# Eth.net
KiCad netlist of a schematic drawn in Altium Designer
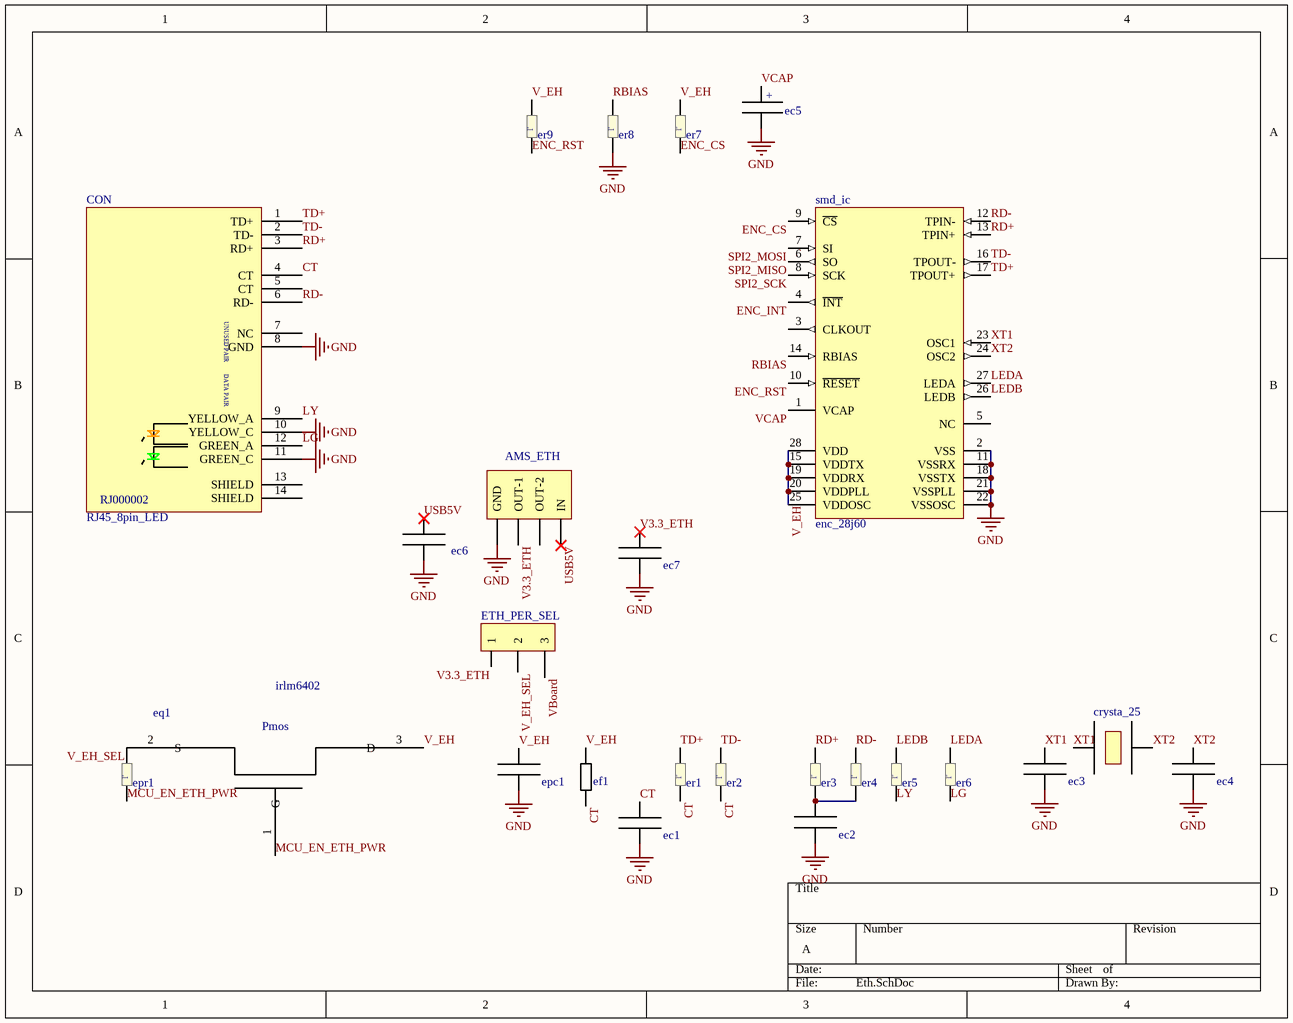
[diagram p0: Eth.SchDoc]

(export (version "E")
  (design (tool "Eeschema 10.0.6"))
  (components
    (comp (ref "AMS_ETH")
      (value "Regulator")
      (footprint "abr_fp_SOT-223_3d")
      (libsource (lib "abr_reg_smd-96-04") (part "abr_reg_AMS1117"))
    )
    (comp (ref "CON")
      (value "RJ45_8pin_LED")
      (footprint "abr_eth_RJ45_8pin_LED_3d")
      (libsource (lib "ethlib") (part "RJ45_8pin_LED"))
    )
    (comp (ref "crysta_25")
      (value "crystal")
      (footprint "abr_crystal_dip_3d")
      (libsource (lib "abr_crystal_osc_96_02") (part "abr_crystal"))
    )
    (comp (ref "ec1")
      (value "100nf")
      (footprint "abr_cap_0805_3d")
      (libsource (lib "abr_smd_0805_all") (part "abr_cap_0805"))
    )
    (comp (ref "ec2")
      (value "100nf")
      (footprint "abr_cap_0805_3d")
      (libsource (lib "abr_smd_0805_all") (part "abr_cap_0805"))
    )
    (comp (ref "ec3")
      (value "100nf")
      (footprint "abr_cap_0805_3d")
      (libsource (lib "abr_smd_0805_all") (part "abr_cap_0805"))
    )
    (comp (ref "ec4")
      (value "100nf")
      (footprint "abr_cap_0805_3d")
      (libsource (lib "abr_smd_0805_all") (part "abr_cap_0805"))
    )
    (comp (ref "ec5")
      (value "10uf")
      (footprint "abr_cap_a_3d")
      (libsource (lib "abr_capasitor") (part "abr_cap"))
    )
    (comp (ref "ec6")
      (value "1uf")
      (footprint "abr_cap_0805_3d")
      (libsource (lib "abr_smd_0805_all") (part "abr_cap_0805"))
    )
    (comp (ref "ec7")
      (value "1uf")
      (footprint "abr_cap_0805_3d")
      (libsource (lib "abr_smd_0805_all") (part "abr_cap_0805"))
    )
    (comp (ref "ef1")
      (value "smd-0805")
      (footprint "abr_fer_0805_3d")
      (libsource (lib "abr_smd_0805_all") (part "abr_fer_0805"))
    )
    (comp (ref "epc1")
      (value "100nf")
      (footprint "abr_cap_0805_3d")
      (libsource (lib "abr_smd_0805_all") (part "abr_cap_0805"))
    )
    (comp (ref "epr1")
      (value "10k")
      (footprint "abr_res_0805_3d")
      (libsource (lib "abr_smd_0805_all") (part "abr_res_0805"))
    )
    (comp (ref "eq1")
      (value "irlm6402")
      (footprint "irlm6402")
      (libsource (lib "abr_transistor_smd") (part "irlm6402"))
    )
    (comp (ref "er1")
      (value "49.9")
      (footprint "abr_res_0805_3d")
      (libsource (lib "abr_smd_0805_all") (part "abr_res_0805"))
    )
    (comp (ref "er2")
      (value "49.9")
      (footprint "abr_res_0805_3d")
      (libsource (lib "abr_smd_0805_all") (part "abr_res_0805"))
    )
    (comp (ref "er3")
      (value "49.9")
      (footprint "abr_res_0805_3d")
      (libsource (lib "abr_smd_0805_all") (part "abr_res_0805"))
    )
    (comp (ref "er4")
      (value "49.9")
      (footprint "abr_res_0805_3d")
      (libsource (lib "abr_smd_0805_all") (part "abr_res_0805"))
    )
    (comp (ref "er5")
      (value "1k")
      (footprint "abr_res_0805_3d")
      (libsource (lib "abr_smd_0805_all") (part "abr_res_0805"))
    )
    (comp (ref "er6")
      (value "1k")
      (footprint "abr_res_0805_3d")
      (libsource (lib "abr_smd_0805_all") (part "abr_res_0805"))
    )
    (comp (ref "er7")
      (value "10k")
      (footprint "abr_res_0805_3d")
      (libsource (lib "abr_smd_0805_all") (part "abr_res_0805"))
    )
    (comp (ref "er8")
      (value "2.3k")
      (footprint "abr_res_0805_3d")
      (libsource (lib "abr_smd_0805_all") (part "abr_res_0805"))
    )
    (comp (ref "er9")
      (value "10k")
      (footprint "abr_res_0805_3d")
      (libsource (lib "abr_smd_0805_all") (part "abr_res_0805"))
    )
    (comp (ref "ETH_PER_SEL")
      (value "pin header 2mm")
      (footprint "abr_ph_3x1_2mm_2d_male")
      (libsource (lib "abr_ph_2mm_96_02") (part "abr_ph_3x1_2mm"))
    )
    (comp (ref "smd_ic")
      (value "enc_28j60")
      (footprint "abr_eth_enc28j60_3d")
      (libsource (lib "ethlib") (part "enc_28j60"))
    )
  )
  (nets
    (net (code "1") (name "/CT") (class "Default")
      (node (ref "CON") (pin "4") (pinfunction "CT_4") (pintype "passive"))
      (node (ref "ec1") (pin "1") (pinfunction "10_1") (pintype "passive"))
      (node (ref "ef1") (pin "1") (pinfunction "2_1") (pintype "passive"))
      (node (ref "er1") (pin "0") (pinfunction "0_0") (pintype "passive"))
      (node (ref "er2") (pin "0") (pinfunction "0_0") (pintype "passive"))
    )
    (net (code "2") (name "/ENC_CS") (class "Default")
      (node (ref "er7") (pin "0") (pinfunction "0_0") (pintype "passive"))
      (node (ref "smd_ic") (pin "9") (pinfunction "~{CS}_9") (pintype "input"))
    )
    (net (code "3") (name "/ENC_INT") (class "Default")
      (node (ref "smd_ic") (pin "4") (pinfunction "~{INT}_4") (pintype "output"))
    )
    (net (code "4") (name "/ENC_RST") (class "Default")
      (node (ref "er9") (pin "0") (pinfunction "0_0") (pintype "passive"))
      (node (ref "smd_ic") (pin "10") (pinfunction "~{RESET}_10") (pintype "input"))
    )
    (net (code "5") (name "/LEDA") (class "Default")
      (node (ref "er6") (pin "1") (pinfunction "0_1") (pintype "passive"))
      (node (ref "smd_ic") (pin "27") (pinfunction "LEDA_27") (pintype "output"))
    )
    (net (code "6") (name "/LEDB") (class "Default")
      (node (ref "er5") (pin "1") (pinfunction "0_1") (pintype "passive"))
      (node (ref "smd_ic") (pin "26") (pinfunction "LEDB_26") (pintype "output"))
    )
    (net (code "7") (name "/LG") (class "Default")
      (node (ref "CON") (pin "12") (pinfunction "GREEN_A_12") (pintype "passive"))
      (node (ref "er6") (pin "0") (pinfunction "0_0") (pintype "passive"))
    )
    (net (code "8") (name "/LY") (class "Default")
      (node (ref "CON") (pin "9") (pinfunction "YELLOW_A_9") (pintype "passive"))
      (node (ref "er5") (pin "0") (pinfunction "0_0") (pintype "passive"))
    )
    (net (code "9") (name "/MCU_EN_ETH_PWR") (class "Default")
      (node (ref "epr1") (pin "0") (pinfunction "0_0") (pintype "passive"))
      (node (ref "eq1") (pin "1") (pinfunction "G_1") (pintype "passive"))
    )
    (net (code "10") (name "/RBIAS") (class "Default")
      (node (ref "er8") (pin "1") (pinfunction "0_1") (pintype "passive"))
      (node (ref "smd_ic") (pin "14") (pinfunction "RBIAS_14") (pintype "input"))
    )
    (net (code "11") (name "/RD+") (class "Default")
      (node (ref "CON") (pin "3") (pinfunction "RD+_3") (pintype "passive"))
      (node (ref "er3") (pin "1") (pinfunction "0_1") (pintype "passive"))
      (node (ref "smd_ic") (pin "13") (pinfunction "TPIN+_13") (pintype "input"))
    )
    (net (code "12") (name "/RD-") (class "Default")
      (node (ref "CON") (pin "6") (pinfunction "RD-_6") (pintype "passive"))
      (node (ref "er4") (pin "1") (pinfunction "0_1") (pintype "passive"))
      (node (ref "smd_ic") (pin "12") (pinfunction "TPIN-_12") (pintype "input"))
    )
    (net (code "13") (name "/SPI2_MISO") (class "Default")
      (node (ref "smd_ic") (pin "6") (pinfunction "SO_6") (pintype "output"))
    )
    (net (code "14") (name "/SPI2_MOSI") (class "Default")
      (node (ref "smd_ic") (pin "7") (pinfunction "SI_7") (pintype "input"))
    )
    (net (code "15") (name "/SPI2_SCK") (class "Default")
      (node (ref "smd_ic") (pin "8") (pinfunction "SCK_8") (pintype "input"))
    )
    (net (code "16") (name "/TD+") (class "Default")
      (node (ref "CON") (pin "1") (pinfunction "TD+_1") (pintype "passive"))
      (node (ref "er1") (pin "1") (pinfunction "0_1") (pintype "passive"))
      (node (ref "smd_ic") (pin "17") (pinfunction "TPOUT+_17") (pintype "output"))
    )
    (net (code "17") (name "/TD-") (class "Default")
      (node (ref "CON") (pin "2") (pinfunction "TD-_2") (pintype "passive"))
      (node (ref "er2") (pin "1") (pinfunction "0_1") (pintype "passive"))
      (node (ref "smd_ic") (pin "16") (pinfunction "TPOUT-_16") (pintype "output"))
    )
    (net (code "18") (name "/USB5V") (class "Default")
      (node (ref "AMS_ETH") (pin "3") (pinfunction "IN_3") (pintype "passive"))
      (node (ref "ec6") (pin "1") (pinfunction "10_1") (pintype "passive"))
    )
    (net (code "19") (name "/V3.3_ETH") (class "Default")
      (node (ref "AMS_ETH") (pin "2") (pinfunction "OUT-1_2") (pintype "passive"))
      (node (ref "ETH_PER_SEL") (pin "1") (pinfunction "1_1") (pintype "passive"))
      (node (ref "ec7") (pin "1") (pinfunction "10_1") (pintype "passive"))
    )
    (net (code "20") (name "/VBoard") (class "Default")
      (node (ref "ETH_PER_SEL") (pin "3") (pinfunction "3_3") (pintype "passive"))
    )
    (net (code "21") (name "/VCAP") (class "Default")
      (node (ref "ec5") (pin "0") (pinfunction "+_0") (pintype "passive"))
      (node (ref "smd_ic") (pin "1") (pinfunction "VCAP_1") (pintype "power_in"))
    )
    (net (code "22") (name "/V_EH") (class "Default")
      (node (ref "ef1") (pin "0") (pinfunction "1_0") (pintype "passive"))
      (node (ref "epc1") (pin "1") (pinfunction "10_1") (pintype "passive"))
      (node (ref "eq1") (pin "3") (pinfunction "D_3") (pintype "passive"))
      (node (ref "er7") (pin "1") (pinfunction "0_1") (pintype "passive"))
      (node (ref "er9") (pin "1") (pinfunction "0_1") (pintype "passive"))
      (node (ref "smd_ic") (pin "15") (pinfunction "VDDTX_15") (pintype "power_in"))
      (node (ref "smd_ic") (pin "19") (pinfunction "VDDRX_19") (pintype "power_in"))
      (node (ref "smd_ic") (pin "20") (pinfunction "VDDPLL_20") (pintype "power_in"))
      (node (ref "smd_ic") (pin "25") (pinfunction "VDDOSC_25") (pintype "power_in"))
      (node (ref "smd_ic") (pin "28") (pinfunction "VDD_28") (pintype "power_in"))
    )
    (net (code "23") (name "/V_EH_SEL") (class "Default")
      (node (ref "ETH_PER_SEL") (pin "2") (pinfunction "2_2") (pintype "passive"))
      (node (ref "epr1") (pin "1") (pinfunction "0_1") (pintype "passive"))
      (node (ref "eq1") (pin "2") (pinfunction "S_2") (pintype "passive"))
    )
    (net (code "24") (name "/XT1") (class "Default")
      (node (ref "crysta_25") (pin "1") (pintype "passive"))
      (node (ref "ec3") (pin "1") (pinfunction "10_1") (pintype "passive"))
      (node (ref "smd_ic") (pin "23") (pinfunction "OSC1_23") (pintype "input"))
    )
    (net (code "25") (name "/XT2") (class "Default")
      (node (ref "crysta_25") (pin "2") (pintype "passive"))
      (node (ref "ec4") (pin "1") (pinfunction "10_1") (pintype "passive"))
      (node (ref "smd_ic") (pin "24") (pinfunction "OSC2_24") (pintype "output"))
    )
    (net (code "26") (name "GND") (class "Default")
      (node (ref "AMS_ETH") (pin "1") (pinfunction "GND_1") (pintype "passive"))
      (node (ref "CON") (pin "10") (pinfunction "YELLOW_C_10") (pintype "passive"))
      (node (ref "CON") (pin "11") (pinfunction "GREEN_C_11") (pintype "passive"))
      (node (ref "CON") (pin "8") (pinfunction "GND_8") (pintype "passive"))
      (node (ref "ec1") (pin "0") (pinfunction "2_0") (pintype "passive"))
      (node (ref "ec2") (pin "0") (pinfunction "2_0") (pintype "passive"))
      (node (ref "ec3") (pin "0") (pinfunction "2_0") (pintype "passive"))
      (node (ref "ec4") (pin "0") (pinfunction "2_0") (pintype "passive"))
      (node (ref "ec5") (pin "1") (pinfunction "1_1") (pintype "passive"))
      (node (ref "ec6") (pin "0") (pinfunction "2_0") (pintype "passive"))
      (node (ref "ec7") (pin "0") (pinfunction "2_0") (pintype "passive"))
      (node (ref "epc1") (pin "0") (pinfunction "2_0") (pintype "passive"))
      (node (ref "er8") (pin "0") (pinfunction "0_0") (pintype "passive"))
      (node (ref "smd_ic") (pin "11") (pinfunction "VSSRX_11") (pintype "power_in"))
      (node (ref "smd_ic") (pin "18") (pinfunction "VSSTX_18") (pintype "power_in"))
      (node (ref "smd_ic") (pin "2") (pinfunction "VSS_2") (pintype "power_in"))
      (node (ref "smd_ic") (pin "21") (pinfunction "VSSPLL_21") (pintype "power_in"))
      (node (ref "smd_ic") (pin "22") (pinfunction "VSSOSC_22") (pintype "power_in"))
    )
    (net (code "27") (name "Net-(ec2-10)") (class "Default")
      (node (ref "ec2") (pin "1") (pinfunction "10_1") (pintype "passive"))
      (node (ref "er3") (pin "0") (pinfunction "0_0") (pintype "passive"))
      (node (ref "er4") (pin "0") (pinfunction "0_0") (pintype "passive"))
    )
    (net (code "28") (name "unconnected-(AMS_ETH-OUT-2-Pad4)") (class "Default")
      (node (ref "AMS_ETH") (pin "4") (pinfunction "OUT-2_4") (pintype "passive"))
    )
    (net (code "29") (name "unconnected-(CON-CT-Pad5)") (class "Default")
      (node (ref "CON") (pin "5") (pinfunction "CT_5") (pintype "passive"))
    )
    (net (code "30") (name "unconnected-(CON-NC-Pad7)") (class "Default")
      (node (ref "CON") (pin "7") (pinfunction "NC_7") (pintype "passive"))
    )
    (net (code "31") (name "unconnected-(CON-SHIELD-Pad13)") (class "Default")
      (node (ref "CON") (pin "13") (pinfunction "SHIELD_13") (pintype "passive"))
    )
    (net (code "32") (name "unconnected-(CON-SHIELD-Pad14)") (class "Default")
      (node (ref "CON") (pin "14") (pinfunction "SHIELD_14") (pintype "passive"))
    )
    (net (code "33") (name "unconnected-(smd_ic-CLKOUT-Pad3)") (class "Default")
      (node (ref "smd_ic") (pin "3") (pinfunction "CLKOUT_3") (pintype "output"))
    )
    (net (code "34") (name "unconnected-(smd_ic-NC-Pad5)") (class "Default")
      (node (ref "smd_ic") (pin "5") (pinfunction "NC_5") (pintype "passive"))
    )
  )
)
